# PMNv1-1H.net
KiCad netlist of a schematic drawn in EAGLE
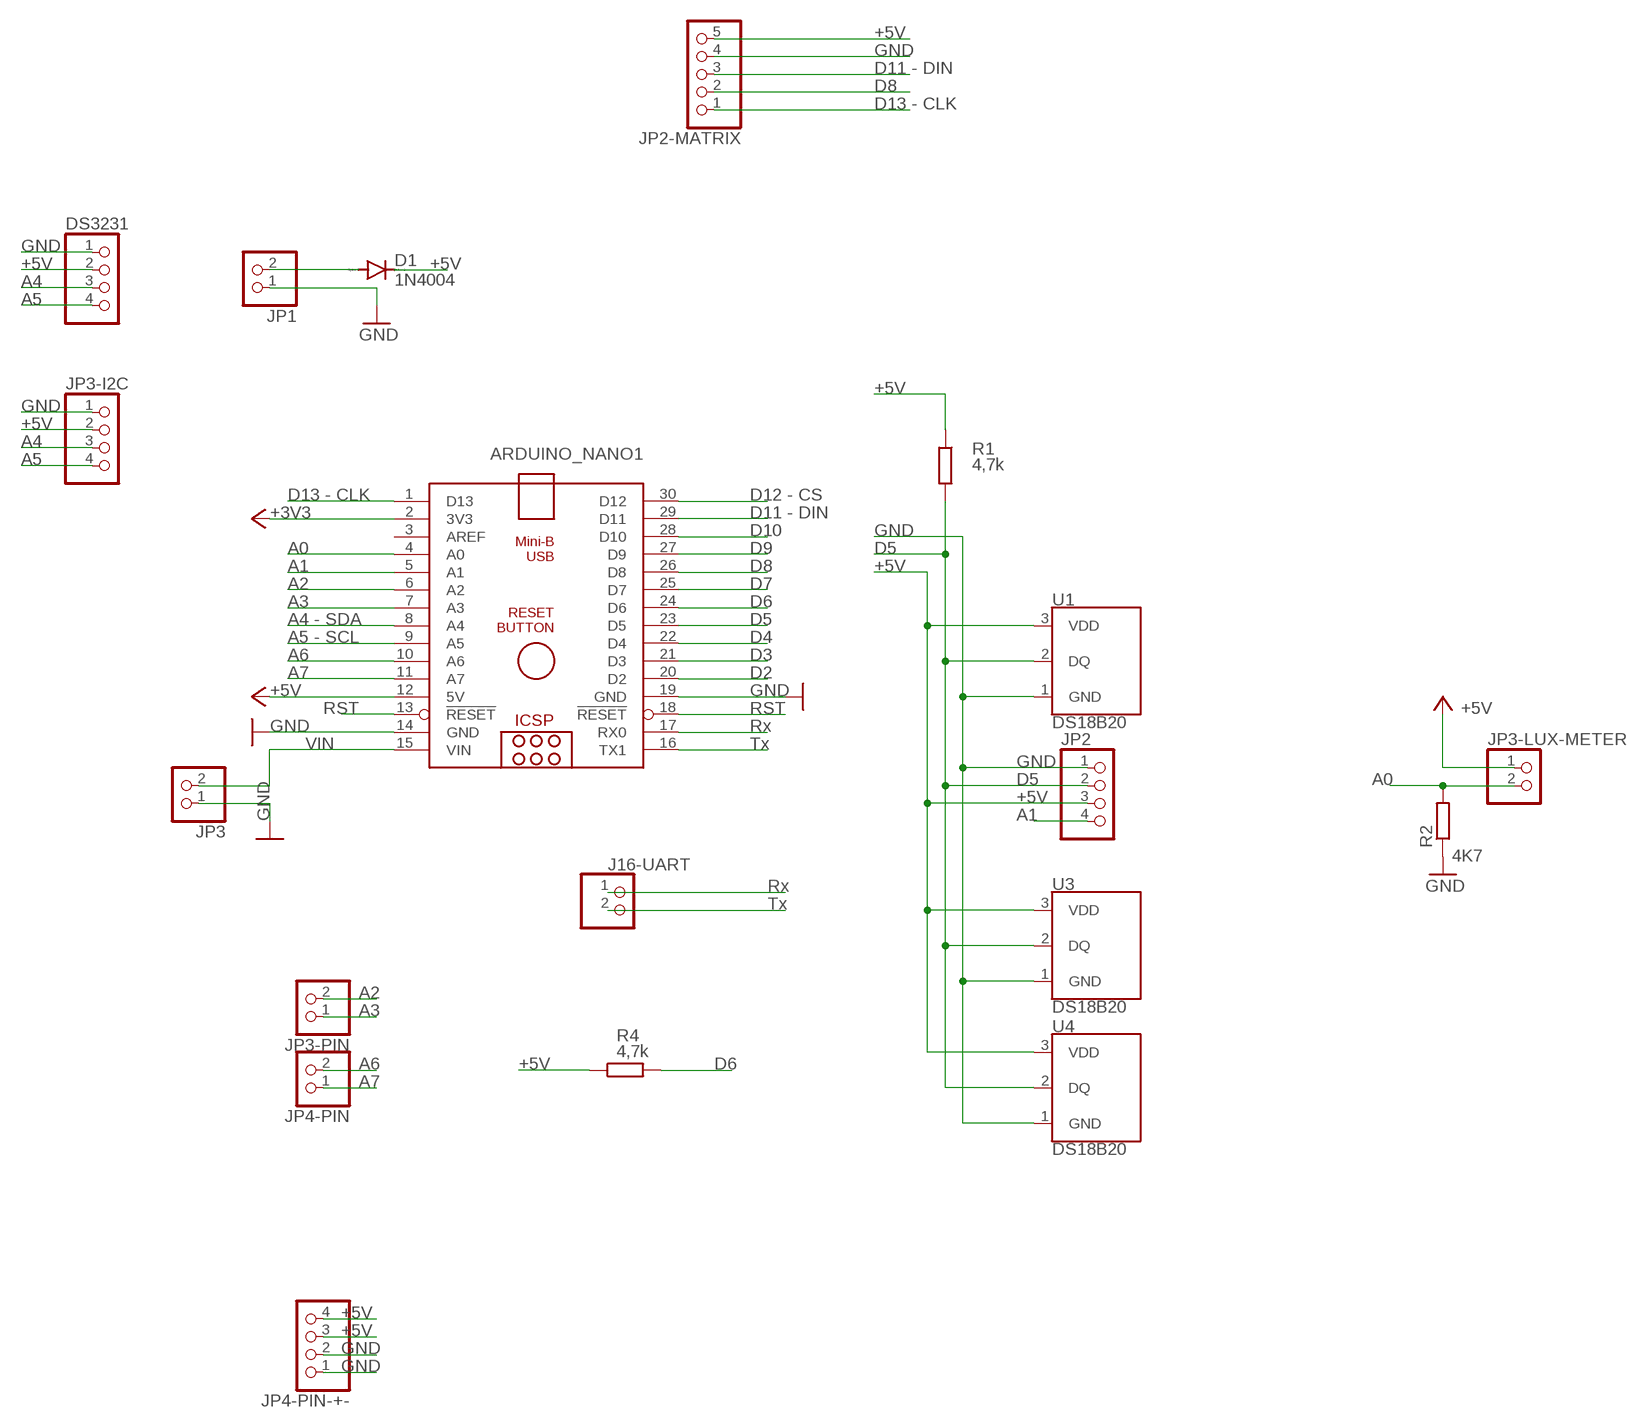
[diagram p0: schematic, sheet 1]

(export (version "E")
  (design (tool "Eeschema 10.0.6"))
  (components
    (comp (ref "ARDUINO_NANO1")
      (value "ARDUINO_NANO")
      (footprint "eagle-import:ARDUINO_NANO")
      (libsource (lib "eagle-import") (part "ARDUINO_NANO"))
    )
    (comp (ref "D1")
      (value "1N4004")
      (footprint "eagle-import:DO41-10")
      (libsource (lib "eagle-import") (part "1N4004"))
    )
    (comp (ref "DS3231")
      (value "PINHD-1X4")
      (footprint "eagle-import:1X04")
      (libsource (lib "eagle-import") (part "PINHD-1X4"))
    )
    (comp (ref "J16-UART")
      (value "PINHD-1X2")
      (footprint "eagle-import:1X02")
      (libsource (lib "eagle-import") (part "PINHD-1X2"))
    )
    (comp (ref "JP1")
      (value "PINHD-1X2")
      (footprint "eagle-import:1X02")
      (libsource (lib "eagle-import") (part "PINHD-1X2"))
    )
    (comp (ref "JP2")
      (value "PINHD-1X4")
      (footprint "eagle-import:1X04")
      (libsource (lib "eagle-import") (part "PINHD-1X4"))
    )
    (comp (ref "JP2-MATRIX")
      (value "PINHD-1X5")
      (footprint "eagle-import:1X05")
      (libsource (lib "eagle-import") (part "PINHD-1X5"))
    )
    (comp (ref "JP3")
      (value "PINHD-1X2")
      (footprint "eagle-import:1X02")
      (libsource (lib "eagle-import") (part "PINHD-1X2"))
    )
    (comp (ref "JP3-I2C")
      (value "PINHD-1X4")
      (footprint "eagle-import:1X04")
      (libsource (lib "eagle-import") (part "PINHD-1X4"))
    )
    (comp (ref "JP3-LUX-METER")
      (value "PINHD-1X2")
      (footprint "eagle-import:1X02")
      (libsource (lib "eagle-import") (part "PINHD-1X2"))
    )
    (comp (ref "JP3-PIN")
      (value "PINHD-1X2")
      (footprint "eagle-import:1X02")
      (libsource (lib "eagle-import") (part "PINHD-1X2"))
    )
    (comp (ref "JP4-PIN")
      (value "PINHD-1X2")
      (footprint "eagle-import:1X02")
      (libsource (lib "eagle-import") (part "PINHD-1X2"))
    )
    (comp (ref "JP4-PIN-+-")
      (value "PINHD-1X4")
      (footprint "eagle-import:1X04")
      (libsource (lib "eagle-import") (part "PINHD-1X4"))
    )
    (comp (ref "R1")
      (value "4,7k")
      (footprint "eagle-import:0204_7")
      (libsource (lib "eagle-import") (part "R-EU_0204/7"))
    )
    (comp (ref "R2")
      (value "4K7")
      (footprint "eagle-import:0207_10")
      (libsource (lib "eagle-import") (part "rcl_334_R-EU_0207/10"))
    )
    (comp (ref "R4")
      (value "4,7k")
      (footprint "eagle-import:0204_7")
      (libsource (lib "eagle-import") (part "R-EU_0204/7"))
    )
    (comp (ref "U1")
      (value "DS18B20")
      (footprint "eagle-import:TO-92-AMMO")
      (libsource (lib "eagle-import") (part "DS18B20"))
    )
    (comp (ref "U3")
      (value "DS18B20")
      (footprint "eagle-import:TO-92-AMMO")
      (libsource (lib "eagle-import") (part "DS18B20"))
    )
    (comp (ref "U4")
      (value "DS18B20")
      (footprint "eagle-import:TO-92-AMMO")
      (libsource (lib "eagle-import") (part "DS18B20"))
    )
  )
  (nets
    (net (code "1") (name "+3V3") (class "Default")
      (node (ref "ARDUINO_NANO1") (pin "2") (pinfunction "3V3_2") (pintype "output"))
    )
    (net (code "2") (name "+5V") (class "Default")
      (node (ref "ARDUINO_NANO1") (pin "12") (pinfunction "5V_12") (pintype "power_in"))
      (node (ref "D1") (pin "C") (pinfunction "C_C") (pintype "passive"))
      (node (ref "DS3231") (pin "2") (pinfunction "2_2") (pintype "passive"))
      (node (ref "JP2") (pin "3") (pinfunction "3_3") (pintype "passive"))
      (node (ref "JP2-MATRIX") (pin "5") (pinfunction "5_5") (pintype "passive"))
      (node (ref "JP3-I2C") (pin "2") (pinfunction "2_2") (pintype "passive"))
      (node (ref "JP3-LUX-METER") (pin "1") (pinfunction "1_1") (pintype "passive"))
      (node (ref "JP4-PIN-+-") (pin "3") (pinfunction "3_3") (pintype "passive"))
      (node (ref "JP4-PIN-+-") (pin "4") (pinfunction "4_4") (pintype "passive"))
      (node (ref "R1") (pin "1") (pinfunction "1_1") (pintype "passive"))
      (node (ref "R4") (pin "1") (pinfunction "1_1") (pintype "passive"))
      (node (ref "U1") (pin "3") (pinfunction "VDD_3") (pintype "power_in"))
      (node (ref "U3") (pin "3") (pinfunction "VDD_3") (pintype "power_in"))
      (node (ref "U4") (pin "3") (pinfunction "VDD_3") (pintype "power_in"))
    )
    (net (code "3") (name "/A0") (class "Default")
      (node (ref "ARDUINO_NANO1") (pin "4") (pinfunction "A0_4") (pintype "bidirectional"))
      (node (ref "JP3-LUX-METER") (pin "2") (pinfunction "2_2") (pintype "passive"))
      (node (ref "R2") (pin "2") (pinfunction "2_2") (pintype "passive"))
    )
    (net (code "4") (name "/A1") (class "Default")
      (node (ref "ARDUINO_NANO1") (pin "5") (pinfunction "A1_5") (pintype "bidirectional"))
      (node (ref "JP2") (pin "4") (pinfunction "4_4") (pintype "passive"))
    )
    (net (code "5") (name "/A2") (class "Default")
      (node (ref "ARDUINO_NANO1") (pin "6") (pinfunction "A2_6") (pintype "bidirectional"))
      (node (ref "JP3-PIN") (pin "2") (pinfunction "2_2") (pintype "passive"))
    )
    (net (code "6") (name "/A3") (class "Default")
      (node (ref "ARDUINO_NANO1") (pin "7") (pinfunction "A3_7") (pintype "bidirectional"))
      (node (ref "JP3-PIN") (pin "1") (pinfunction "1_1") (pintype "passive"))
    )
    (net (code "7") (name "/A4") (class "Default")
      (node (ref "ARDUINO_NANO1") (pin "8") (pinfunction "A4_8") (pintype "bidirectional"))
      (node (ref "DS3231") (pin "3") (pinfunction "3_3") (pintype "passive"))
      (node (ref "JP3-I2C") (pin "3") (pinfunction "3_3") (pintype "passive"))
    )
    (net (code "8") (name "/A5") (class "Default")
      (node (ref "ARDUINO_NANO1") (pin "9") (pinfunction "A5_9") (pintype "bidirectional"))
      (node (ref "DS3231") (pin "4") (pinfunction "4_4") (pintype "passive"))
      (node (ref "JP3-I2C") (pin "4") (pinfunction "4_4") (pintype "passive"))
    )
    (net (code "9") (name "/A6") (class "Default")
      (node (ref "ARDUINO_NANO1") (pin "10") (pinfunction "A6_10") (pintype "bidirectional"))
      (node (ref "JP4-PIN") (pin "2") (pinfunction "2_2") (pintype "passive"))
    )
    (net (code "10") (name "/A7") (class "Default")
      (node (ref "ARDUINO_NANO1") (pin "11") (pinfunction "A7_11") (pintype "bidirectional"))
      (node (ref "JP4-PIN") (pin "1") (pinfunction "1_1") (pintype "passive"))
    )
    (net (code "11") (name "/D5") (class "Default")
      (node (ref "ARDUINO_NANO1") (pin "23") (pinfunction "D5_23") (pintype "bidirectional"))
      (node (ref "JP2") (pin "2") (pinfunction "2_2") (pintype "passive"))
      (node (ref "R1") (pin "2") (pinfunction "2_2") (pintype "passive"))
      (node (ref "U1") (pin "2") (pinfunction "DQ_2") (pintype "bidirectional"))
      (node (ref "U3") (pin "2") (pinfunction "DQ_2") (pintype "bidirectional"))
      (node (ref "U4") (pin "2") (pinfunction "DQ_2") (pintype "bidirectional"))
    )
    (net (code "12") (name "/D6") (class "Default")
      (node (ref "ARDUINO_NANO1") (pin "24") (pinfunction "D6_24") (pintype "bidirectional"))
      (node (ref "R4") (pin "2") (pinfunction "2_2") (pintype "passive"))
    )
    (net (code "13") (name "/D8") (class "Default")
      (node (ref "ARDUINO_NANO1") (pin "26") (pinfunction "D8_26") (pintype "bidirectional"))
      (node (ref "JP2-MATRIX") (pin "2") (pinfunction "2_2") (pintype "passive"))
    )
    (net (code "14") (name "/D11") (class "Default")
      (node (ref "ARDUINO_NANO1") (pin "29") (pinfunction "D11_29") (pintype "bidirectional"))
      (node (ref "JP2-MATRIX") (pin "3") (pinfunction "3_3") (pintype "passive"))
    )
    (net (code "15") (name "/D13") (class "Default")
      (node (ref "ARDUINO_NANO1") (pin "1") (pinfunction "D13_1") (pintype "bidirectional"))
      (node (ref "JP2-MATRIX") (pin "1") (pinfunction "1_1") (pintype "passive"))
    )
    (net (code "16") (name "/RST") (class "Default")
      (node (ref "ARDUINO_NANO1") (pin "13") (pinfunction "~{RESET}_13") (pintype "input"))
      (node (ref "ARDUINO_NANO1") (pin "18") (pinfunction "~{RESET}_18") (pintype "input"))
    )
    (net (code "17") (name "/RX") (class "Default")
      (node (ref "ARDUINO_NANO1") (pin "17") (pinfunction "RX0_17") (pintype "bidirectional"))
      (node (ref "J16-UART") (pin "1") (pinfunction "1_1") (pintype "passive"))
    )
    (net (code "18") (name "/TX") (class "Default")
      (node (ref "ARDUINO_NANO1") (pin "16") (pinfunction "TX1_16") (pintype "bidirectional"))
      (node (ref "J16-UART") (pin "2") (pinfunction "2_2") (pintype "passive"))
    )
    (net (code "19") (name "GND") (class "Default")
      (node (ref "ARDUINO_NANO1") (pin "14") (pinfunction "GND_14") (pintype "power_in"))
      (node (ref "ARDUINO_NANO1") (pin "19") (pinfunction "GND_19") (pintype "power_in"))
      (node (ref "DS3231") (pin "1") (pinfunction "1_1") (pintype "passive"))
      (node (ref "JP1") (pin "1") (pinfunction "1_1") (pintype "passive"))
      (node (ref "JP2") (pin "1") (pinfunction "1_1") (pintype "passive"))
      (node (ref "JP2-MATRIX") (pin "4") (pinfunction "4_4") (pintype "passive"))
      (node (ref "JP3") (pin "1") (pinfunction "1_1") (pintype "passive"))
      (node (ref "JP3-I2C") (pin "1") (pinfunction "1_1") (pintype "passive"))
      (node (ref "JP4-PIN-+-") (pin "1") (pinfunction "1_1") (pintype "passive"))
      (node (ref "JP4-PIN-+-") (pin "2") (pinfunction "2_2") (pintype "passive"))
      (node (ref "R2") (pin "1") (pinfunction "1_1") (pintype "passive"))
      (node (ref "U1") (pin "1") (pinfunction "GND_1") (pintype "power_in"))
      (node (ref "U3") (pin "1") (pinfunction "GND_1") (pintype "power_in"))
      (node (ref "U4") (pin "1") (pinfunction "GND_1") (pintype "power_in"))
    )
    (net (code "20") (name "Net-(ARDUINO_NANO1-VIN)") (class "Default")
      (node (ref "ARDUINO_NANO1") (pin "15") (pinfunction "VIN_15") (pintype "power_in"))
      (node (ref "JP3") (pin "2") (pinfunction "2_2") (pintype "passive"))
    )
    (net (code "21") (name "Net-(D1-PadA)") (class "Default")
      (node (ref "D1") (pin "A") (pinfunction "A_A") (pintype "passive"))
      (node (ref "JP1") (pin "2") (pinfunction "2_2") (pintype "passive"))
    )
    (net (code "22") (name "unconnected-(ARDUINO_NANO1-AREF-Pad3)") (class "Default")
      (node (ref "ARDUINO_NANO1") (pin "3") (pinfunction "AREF_3") (pintype "input"))
    )
    (net (code "23") (name "unconnected-(ARDUINO_NANO1-D2-Pad20)") (class "Default")
      (node (ref "ARDUINO_NANO1") (pin "20") (pinfunction "D2_20") (pintype "bidirectional"))
    )
    (net (code "24") (name "unconnected-(ARDUINO_NANO1-D3-Pad21)") (class "Default")
      (node (ref "ARDUINO_NANO1") (pin "21") (pinfunction "D3_21") (pintype "bidirectional"))
    )
    (net (code "25") (name "unconnected-(ARDUINO_NANO1-D4-Pad22)") (class "Default")
      (node (ref "ARDUINO_NANO1") (pin "22") (pinfunction "D4_22") (pintype "bidirectional"))
    )
    (net (code "26") (name "unconnected-(ARDUINO_NANO1-D7-Pad25)") (class "Default")
      (node (ref "ARDUINO_NANO1") (pin "25") (pinfunction "D7_25") (pintype "bidirectional"))
    )
    (net (code "27") (name "unconnected-(ARDUINO_NANO1-D9-Pad27)") (class "Default")
      (node (ref "ARDUINO_NANO1") (pin "27") (pinfunction "D9_27") (pintype "bidirectional"))
    )
    (net (code "28") (name "unconnected-(ARDUINO_NANO1-D10-Pad28)") (class "Default")
      (node (ref "ARDUINO_NANO1") (pin "28") (pinfunction "D10_28") (pintype "bidirectional"))
    )
    (net (code "29") (name "unconnected-(ARDUINO_NANO1-D12-Pad30)") (class "Default")
      (node (ref "ARDUINO_NANO1") (pin "30") (pinfunction "D12_30") (pintype "bidirectional"))
    )
  )
)
